# esptoy_v124.net
KiCad netlist of a schematic drawn in EAGLE
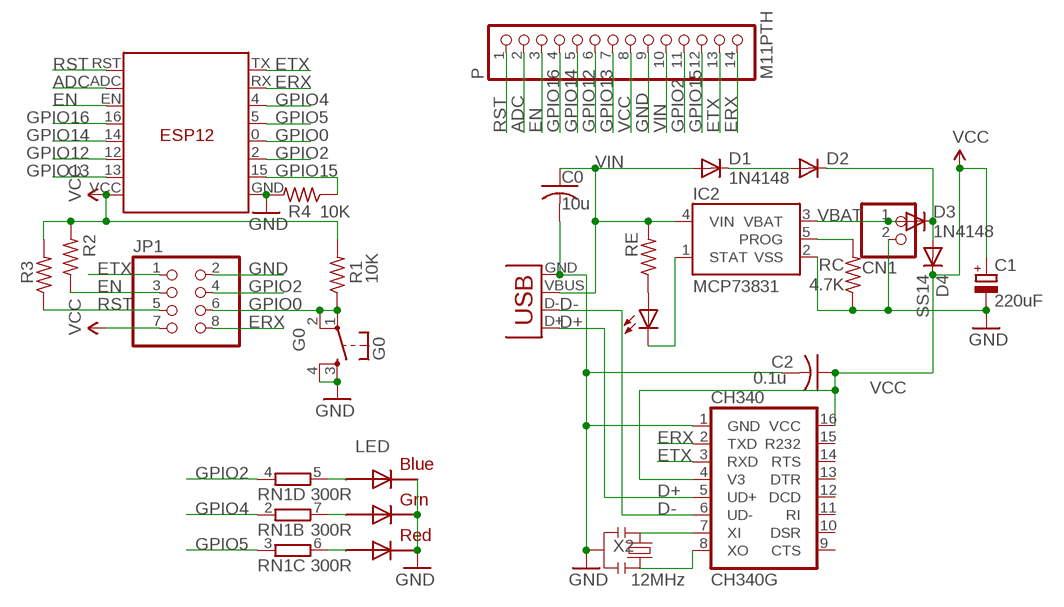
[diagram p0: schematic, sheet 1]

(export (version "E")
  (design (tool "Eeschema 10.0.6"))
  (components
    (comp (ref "C0")
      (value "10u")
      (footprint "eagle-import:C0805K")
      (libsource (lib "eagle-import") (part "adafruit2013_C-USC0805K"))
    )
    (comp (ref "C1")
      (value "220uF")
      (footprint "eagle-import:PANASONIC_D")
      (libsource (lib "eagle-import") (part "CPOL-EUD"))
    )
    (comp (ref "C2")
      (value "0.1u")
      (footprint "eagle-import:C0603K")
      (libsource (lib "eagle-import") (part "C-USC0603K"))
    )
    (comp (ref "CH340")
      (value "CH340G")
      (footprint "eagle-import:SO16")
      (libsource (lib "eagle-import") (part "CH340G"))
    )
    (comp (ref "CHG")
      (value "0805")
      (footprint "eagle-import:CHIPLED_0805")
      (libsource (lib "eagle-import") (part "LEDCHIPLED_0805"))
    )
    (comp (ref "CN1")
      (value "JST_2PIN-SMT-RA")
      (footprint "eagle-import:JST-PH-2-SMT-RA")
      (libsource (lib "eagle-import") (part "JST_2PIN-SMT-RA"))
    )
    (comp (ref "D1")
      (value "1N4148")
      (footprint "eagle-import:MINIMELF")
      (libsource (lib "eagle-import") (part "DIODE-MINIMELF"))
    )
    (comp (ref "D2")
      (value "DIODE-MINIMELF")
      (footprint "eagle-import:MINIMELF")
      (libsource (lib "eagle-import") (part "DIODE-MINIMELF"))
    )
    (comp (ref "D3")
      (value "1N4148")
      (footprint "eagle-import:MINIMELF")
      (libsource (lib "eagle-import") (part "DIODE-MINIMELF"))
    )
    (comp (ref "D4")
      (value "SS14")
      (footprint "eagle-import:DO-214AC")
      (libsource (lib "eagle-import") (part "DIODE-DO-214AC"))
    )
    (comp (ref "G0")
      (value "G0")
      (footprint "eagle-import:TACTILE_SWITCH_SMD")
      (libsource (lib "eagle-import") (part "TAC_SWITCHSMD"))
    )
    (comp (ref "IC2")
      (value "MCP73831")
      (footprint "eagle-import:SOT23-5")
      (libsource (lib "eagle-import") (part "MCP73831"))
    )
    (comp (ref "JP1")
      (value "PINHD-2X4")
      (footprint "eagle-import:2X04")
      (libsource (lib "eagle-import") (part "PINHD-2X4"))
    )
    (comp (ref "LED")
      (value "RGBLED5050")
      (footprint "eagle-import:RGBLED5050")
      (libsource (lib "eagle-import") (part "RGBLED5050"))
    )
    (comp (ref "P")
      (value "M11PTH")
      (footprint "eagle-import:1X14-CB")
      (libsource (lib "eagle-import") (part "PINHD-1X14-CB"))
    )
    (comp (ref "R1")
      (value "10K")
      (footprint "eagle-import:R0603")
      (libsource (lib "eagle-import") (part "R-US_R0603"))
    )
    (comp (ref "R2")
      (value "R-US_R0603")
      (footprint "eagle-import:R0603")
      (libsource (lib "eagle-import") (part "R-US_R0603"))
    )
    (comp (ref "R3")
      (value "R-US_R0603")
      (footprint "eagle-import:R0603")
      (libsource (lib "eagle-import") (part "R-US_R0603"))
    )
    (comp (ref "R4")
      (value "10K")
      (footprint "eagle-import:R0603")
      (libsource (lib "eagle-import") (part "R-US_R0603"))
    )
    (comp (ref "RC")
      (value "4.7K")
      (footprint "eagle-import:R0805")
      (libsource (lib "eagle-import") (part "adafruit2013_R-US_R0805"))
    )
    (comp (ref "RE")
      (value "R-US_R0603")
      (footprint "eagle-import:R0603")
      (libsource (lib "eagle-import") (part "R-US_R0603"))
    )
    (comp (ref "RN1")
      (value "300R")
      (footprint "eagle-import:EXB38V")
      (libsource (lib "eagle-import") (part "4R-NEXB38V"))
    )
    (comp (ref "U$1")
      (value "ESP12")
      (footprint "eagle-import:ESP12")
      (libsource (lib "eagle-import") (part "ESP12"))
    )
    (comp (ref "X2")
      (value "12MHz")
      (footprint "eagle-import:RESONATOR-SMD")
      (libsource (lib "eagle-import") (part "RESONATORSMD"))
    )
    (comp (ref "X3")
      (value "USB-MICROB")
      (footprint "eagle-import:USB-MICROB")
      (libsource (lib "eagle-import") (part "USB-MICROB"))
    )
  )
  (nets
    (net (code "1") (name "/ADC") (class "Default")
      (node (ref "P") (pin "2") (pinfunction "2_2") (pintype "passive"))
      (node (ref "U$1") (pin "ADC") (pinfunction "ADC_ADC") (pintype "bidirectional"))
    )
    (net (code "2") (name "/D+") (class "Default")
      (node (ref "CH340") (pin "5") (pinfunction "UD+_5") (pintype "bidirectional"))
      (node (ref "X3") (pin "D+") (pinfunction "D+_D+") (pintype "bidirectional"))
    )
    (net (code "3") (name "/D-") (class "Default")
      (node (ref "CH340") (pin "6") (pinfunction "UD-_6") (pintype "bidirectional"))
      (node (ref "X3") (pin "D-") (pinfunction "D-_D-") (pintype "bidirectional"))
    )
    (net (code "4") (name "/EN") (class "Default")
      (node (ref "JP1") (pin "3") (pinfunction "3_3") (pintype "passive"))
      (node (ref "P") (pin "3") (pinfunction "3_3") (pintype "passive"))
      (node (ref "R2") (pin "1") (pinfunction "1_1") (pintype "passive"))
      (node (ref "U$1") (pin "EN") (pinfunction "EN_EN") (pintype "bidirectional"))
    )
    (net (code "5") (name "/ERX") (class "Default")
      (node (ref "CH340") (pin "2") (pinfunction "TXD_2") (pintype "bidirectional"))
      (node (ref "JP1") (pin "8") (pinfunction "8_8") (pintype "passive"))
      (node (ref "P") (pin "14") (pinfunction "14_14") (pintype "passive"))
      (node (ref "U$1") (pin "RX") (pinfunction "RX_RX") (pintype "bidirectional"))
    )
    (net (code "6") (name "/ETX") (class "Default")
      (node (ref "CH340") (pin "3") (pinfunction "RXD_3") (pintype "bidirectional"))
      (node (ref "JP1") (pin "1") (pinfunction "1_1") (pintype "passive"))
      (node (ref "P") (pin "13") (pinfunction "13_13") (pintype "passive"))
      (node (ref "U$1") (pin "TX") (pinfunction "TX_TX") (pintype "bidirectional"))
    )
    (net (code "7") (name "/GPIO0") (class "Default")
      (node (ref "G0") (pin "1") (pinfunction "1_1") (pintype "passive"))
      (node (ref "G0") (pin "2") (pinfunction "2_2") (pintype "passive"))
      (node (ref "JP1") (pin "6") (pinfunction "6_6") (pintype "passive"))
      (node (ref "R1") (pin "1") (pinfunction "1_1") (pintype "passive"))
      (node (ref "U$1") (pin "0") (pinfunction "G0_0") (pintype "bidirectional"))
    )
    (net (code "8") (name "/GPIO2") (class "Default")
      (node (ref "JP1") (pin "4") (pinfunction "4_4") (pintype "passive"))
      (node (ref "P") (pin "11") (pinfunction "11_11") (pintype "passive"))
      (node (ref "RN1") (pin "4") (pinfunction "1_4") (pintype "passive"))
      (node (ref "U$1") (pin "2") (pinfunction "G2_2") (pintype "bidirectional"))
    )
    (net (code "9") (name "/GPIO4") (class "Default")
      (node (ref "RN1") (pin "2") (pinfunction "1_2") (pintype "passive"))
      (node (ref "U$1") (pin "4") (pinfunction "G4_4") (pintype "bidirectional"))
    )
    (net (code "10") (name "/GPIO5") (class "Default")
      (node (ref "RN1") (pin "3") (pinfunction "1_3") (pintype "passive"))
      (node (ref "U$1") (pin "5") (pinfunction "G5_5") (pintype "bidirectional"))
    )
    (net (code "11") (name "/GPIO12") (class "Default")
      (node (ref "P") (pin "6") (pinfunction "6_6") (pintype "passive"))
      (node (ref "U$1") (pin "12") (pinfunction "G12_12") (pintype "bidirectional"))
    )
    (net (code "12") (name "/GPIO13") (class "Default")
      (node (ref "P") (pin "7") (pinfunction "7_7") (pintype "passive"))
      (node (ref "U$1") (pin "13") (pinfunction "G13_13") (pintype "bidirectional"))
    )
    (net (code "13") (name "/GPIO14") (class "Default")
      (node (ref "P") (pin "5") (pinfunction "5_5") (pintype "passive"))
      (node (ref "U$1") (pin "14") (pinfunction "G14_14") (pintype "bidirectional"))
    )
    (net (code "14") (name "/GPIO15") (class "Default")
      (node (ref "P") (pin "12") (pinfunction "12_12") (pintype "passive"))
      (node (ref "R4") (pin "1") (pinfunction "1_1") (pintype "passive"))
      (node (ref "U$1") (pin "15") (pinfunction "G15_15") (pintype "bidirectional"))
    )
    (net (code "15") (name "/GPIO16") (class "Default")
      (node (ref "P") (pin "4") (pinfunction "4_4") (pintype "passive"))
      (node (ref "U$1") (pin "16") (pinfunction "G16_16") (pintype "bidirectional"))
    )
    (net (code "16") (name "/RST") (class "Default")
      (node (ref "JP1") (pin "5") (pinfunction "5_5") (pintype "passive"))
      (node (ref "P") (pin "1") (pinfunction "1_1") (pintype "passive"))
      (node (ref "R3") (pin "1") (pinfunction "1_1") (pintype "passive"))
      (node (ref "U$1") (pin "RST") (pinfunction "RST_RST") (pintype "bidirectional"))
    )
    (net (code "17") (name "/VBAT") (class "Default")
      (node (ref "CN1") (pin "1") (pinfunction "2_1") (pintype "passive"))
      (node (ref "D3") (pin "A") (pinfunction "A_A") (pintype "passive"))
      (node (ref "IC2") (pin "3") (pinfunction "VBAT_3") (pintype "power_in"))
    )
    (net (code "18") (name "/VIN") (class "Default")
      (node (ref "C0") (pin "1") (pinfunction "1_1") (pintype "passive"))
      (node (ref "D1") (pin "A") (pinfunction "A_A") (pintype "passive"))
      (node (ref "IC2") (pin "4") (pinfunction "VIN_4") (pintype "power_in"))
      (node (ref "P") (pin "10") (pinfunction "10_10") (pintype "passive"))
      (node (ref "RE") (pin "2") (pinfunction "2_2") (pintype "passive"))
      (node (ref "X3") (pin "VBUS") (pinfunction "VBUS_VBUS") (pintype "bidirectional"))
    )
    (net (code "19") (name "GND") (class "Default")
      (node (ref "C0") (pin "2") (pinfunction "2_2") (pintype "passive"))
      (node (ref "C1") (pin "-") (pinfunction "-_-") (pintype "passive"))
      (node (ref "C2") (pin "2") (pinfunction "2_2") (pintype "passive"))
      (node (ref "CH340") (pin "1") (pinfunction "GND_1") (pintype "power_in"))
      (node (ref "CN1") (pin "2") (pinfunction "1_2") (pintype "passive"))
      (node (ref "G0") (pin "3") (pinfunction "3_3") (pintype "passive"))
      (node (ref "G0") (pin "4") (pinfunction "4_4") (pintype "passive"))
      (node (ref "IC2") (pin "2") (pinfunction "VSS_2") (pintype "power_in"))
      (node (ref "JP1") (pin "2") (pinfunction "2_2") (pintype "passive"))
      (node (ref "LED") (pin "4") (pinfunction "BLUE_C_4") (pintype "bidirectional"))
      (node (ref "LED") (pin "5") (pinfunction "RED_C_5") (pintype "bidirectional"))
      (node (ref "LED") (pin "6") (pinfunction "GREEN_C_6") (pintype "bidirectional"))
      (node (ref "P") (pin "9") (pinfunction "9_9") (pintype "passive"))
      (node (ref "R4") (pin "2") (pinfunction "2_2") (pintype "passive"))
      (node (ref "RC") (pin "1") (pinfunction "1_1") (pintype "passive"))
      (node (ref "U$1") (pin "GND") (pinfunction "GND_GND") (pintype "power_in"))
      (node (ref "X2") (pin "2") (pinfunction "2_2") (pintype "passive"))
      (node (ref "X3") (pin "GND") (pinfunction "GND_GND") (pintype "bidirectional"))
    )
    (net (code "20") (name "Net-(CH340-XI)") (class "Default")
      (node (ref "CH340") (pin "7") (pinfunction "XI_7") (pintype "bidirectional"))
      (node (ref "X2") (pin "1") (pinfunction "1_1") (pintype "passive"))
    )
    (net (code "21") (name "Net-(CH340-XO)") (class "Default")
      (node (ref "CH340") (pin "8") (pinfunction "XO_8") (pintype "bidirectional"))
      (node (ref "X2") (pin "3") (pinfunction "3_3") (pintype "passive"))
    )
    (net (code "22") (name "Net-(CHG-PadA)") (class "Default")
      (node (ref "CHG") (pin "A") (pinfunction "A_A") (pintype "passive"))
      (node (ref "RE") (pin "1") (pinfunction "1_1") (pintype "passive"))
    )
    (net (code "23") (name "Net-(D1-PadC)") (class "Default")
      (node (ref "D1") (pin "C") (pinfunction "C_C") (pintype "passive"))
      (node (ref "D2") (pin "A") (pinfunction "A_A") (pintype "passive"))
    )
    (net (code "24") (name "Net-(D2-PadC)") (class "Default")
      (node (ref "D2") (pin "C") (pinfunction "C_C") (pintype "passive"))
      (node (ref "D3") (pin "C") (pinfunction "C_C") (pintype "passive"))
      (node (ref "D4") (pin "A") (pinfunction "A_A") (pintype "passive"))
    )
    (net (code "25") (name "Net-(IC2-PROG)") (class "Default")
      (node (ref "IC2") (pin "5") (pinfunction "PROG_5") (pintype "input"))
      (node (ref "RC") (pin "2") (pinfunction "2_2") (pintype "passive"))
    )
    (net (code "26") (name "Net-(IC2-STAT)") (class "Default")
      (node (ref "CHG") (pin "C") (pinfunction "C_C") (pintype "passive"))
      (node (ref "IC2") (pin "1") (pinfunction "STAT_1") (pintype "output"))
    )
    (net (code "27") (name "Net-(LED-BLUE_A)") (class "Default")
      (node (ref "LED") (pin "3") (pinfunction "BLUE_A_3") (pintype "bidirectional"))
      (node (ref "RN1") (pin "5") (pinfunction "2_5") (pintype "passive"))
    )
    (net (code "28") (name "Net-(LED-GREEN_A)") (class "Default")
      (node (ref "LED") (pin "1") (pinfunction "GREEN_A_1") (pintype "bidirectional"))
      (node (ref "RN1") (pin "7") (pinfunction "2_7") (pintype "passive"))
    )
    (net (code "29") (name "Net-(LED-RED_A)") (class "Default")
      (node (ref "LED") (pin "2") (pinfunction "RED_A_2") (pintype "bidirectional"))
      (node (ref "RN1") (pin "6") (pinfunction "2_6") (pintype "passive"))
    )
    (net (code "30") (name "VCC") (class "Default")
      (node (ref "C1") (pin "+") (pinfunction "+_+") (pintype "passive"))
      (node (ref "C2") (pin "1") (pinfunction "1_1") (pintype "passive"))
      (node (ref "CH340") (pin "16") (pinfunction "VCC_16") (pintype "power_in"))
      (node (ref "CH340") (pin "4") (pinfunction "V3_4") (pintype "bidirectional"))
      (node (ref "D4") (pin "C") (pinfunction "C_C") (pintype "passive"))
      (node (ref "JP1") (pin "7") (pinfunction "7_7") (pintype "passive"))
      (node (ref "P") (pin "8") (pinfunction "8_8") (pintype "passive"))
      (node (ref "R1") (pin "2") (pinfunction "2_2") (pintype "passive"))
      (node (ref "R2") (pin "2") (pinfunction "2_2") (pintype "passive"))
      (node (ref "R3") (pin "2") (pinfunction "2_2") (pintype "passive"))
      (node (ref "U$1") (pin "VCC") (pinfunction "VCC_VCC") (pintype "power_in"))
    )
    (net (code "31") (name "unconnected-(CH340-CTS-Pad9)") (class "Default")
      (node (ref "CH340") (pin "9") (pinfunction "CTS_9") (pintype "bidirectional"))
    )
    (net (code "32") (name "unconnected-(CH340-DCD-Pad12)") (class "Default")
      (node (ref "CH340") (pin "12") (pinfunction "DCD_12") (pintype "bidirectional"))
    )
    (net (code "33") (name "unconnected-(CH340-DSR-Pad10)") (class "Default")
      (node (ref "CH340") (pin "10") (pinfunction "DSR_10") (pintype "bidirectional"))
    )
    (net (code "34") (name "unconnected-(CH340-DTR-Pad13)") (class "Default")
      (node (ref "CH340") (pin "13") (pinfunction "DTR_13") (pintype "bidirectional"))
    )
    (net (code "35") (name "unconnected-(CH340-R232-Pad15)") (class "Default")
      (node (ref "CH340") (pin "15") (pinfunction "R232_15") (pintype "bidirectional"))
    )
    (net (code "36") (name "unconnected-(CH340-RI-Pad11)") (class "Default")
      (node (ref "CH340") (pin "11") (pinfunction "RI_11") (pintype "bidirectional"))
    )
    (net (code "37") (name "unconnected-(CH340-RTS-Pad14)") (class "Default")
      (node (ref "CH340") (pin "14") (pinfunction "RTS_14") (pintype "bidirectional"))
    )
  )
)
